# DHT11.net
KiCad netlist of a schematic drawn in Altium Designer
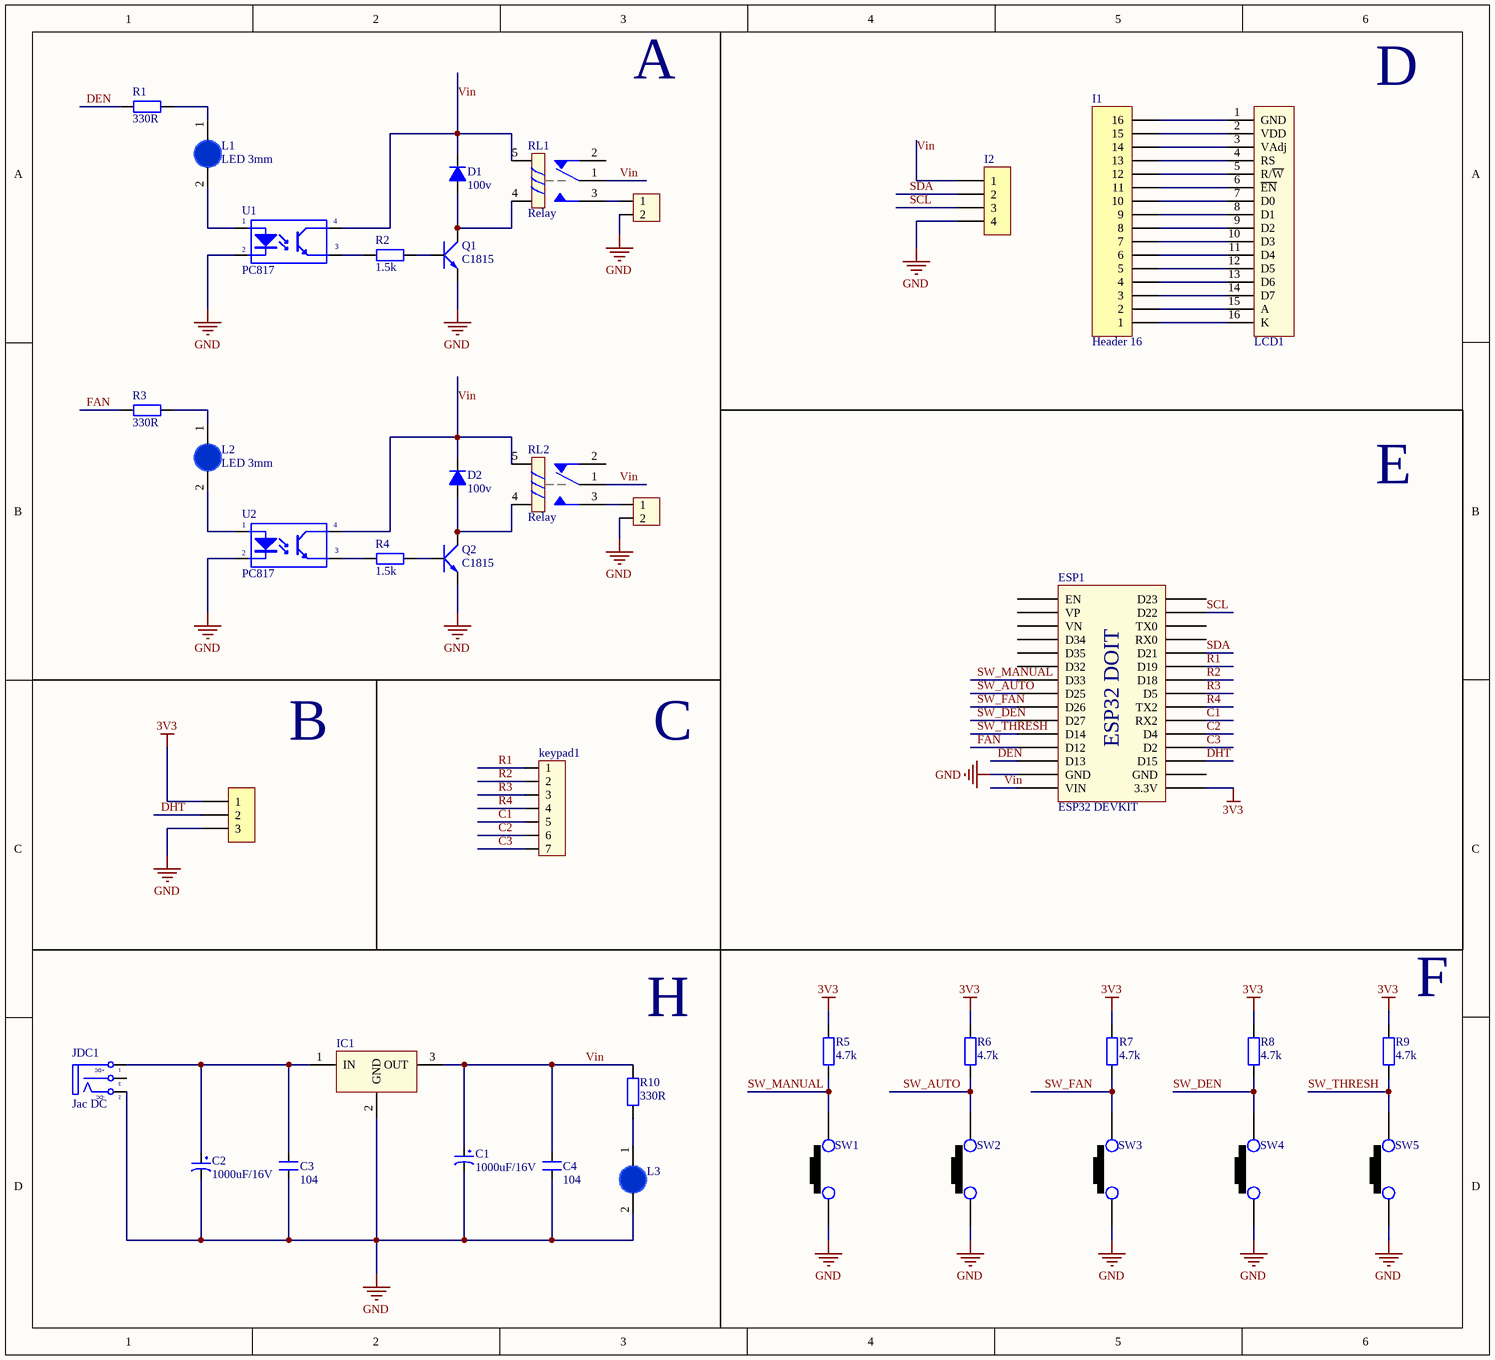
[diagram p0: DHT11.SchDoc]

(export (version "E")
  (design (tool "Eeschema 10.0.6"))
  (components
    (comp (ref "C1")
      (value "1000uF/16V")
      (footprint "CP1.5/3.4")
      (description "Cap 1000uF/16V - 220uF/50V")
      (libsource (lib "syhaunguyen") (part "CP4"))
    )
    (comp (ref "C2")
      (value "1000uF/16V")
      (footprint "CP1.5/3.4")
      (description "Cap 1000uF/16V - 220uF/50V")
      (libsource (lib "syhaunguyen") (part "CP4"))
    )
    (comp (ref "C3")
      (value "104")
      (footprint "CN2")
      (description "Cap np 104 => 105pF")
      (libsource (lib "syhaunguyen") (part "CN2"))
    )
    (comp (ref "C4")
      (value "104")
      (footprint "CN2")
      (description "Cap np 104 => 105pF")
      (libsource (lib "syhaunguyen") (part "CN2"))
    )
    (comp (ref "D1")
      (value "100v")
      (footprint "DIODE 1A")
      (description "Cắm")
      (libsource (lib "Altium_Lib_by_KhueNguyenCreator") (part "Diode 1N4007"))
    )
    (comp (ref "D2")
      (value "100v")
      (footprint "DIODE 1A")
      (description "Cắm")
      (libsource (lib "Altium_Lib_by_KhueNguyenCreator") (part "Diode 1N4007"))
    )
    (comp (ref "ESP1")
      (value "ESP32 DEVKIT")
      (footprint "ESP32 WROOM 32 KIT")
      (libsource (lib "Altium_Lib_by_KhueNguyenCreator") (part "ESP32 WROOM 32 KIT"))
    )
    (comp (ref "H1")
      (value "Header 2P 2.54 Duc Thang")
      (footprint "XH2.54M-2")
      (description "Cắm")
      (libsource (lib "Altium_Lib_by_KhueNguyenCreator") (part "Header 2P 2.54 Duc Thang"))
    )
    (comp (ref "H2")
      (value "Header 2P 2.54 Duc Thang")
      (footprint "XH2.54M-2")
      (description "Cắm")
      (libsource (lib "Altium_Lib_by_KhueNguyenCreator") (part "Header 2P 2.54 Duc Thang"))
    )
    (comp (ref "H3")
      (value "Header 3P 2.54 Duc Thang")
      (footprint "XH2.54M-3")
      (description "Cắm")
      (libsource (lib "Altium_Lib_by_KhueNguyenCreator") (part "Header 3P 2.54 Duc Thang"))
    )
    (comp (ref "I1")
      (value "Header 16")
      (footprint "HDR1X16")
      (description "Header, 16-Pin")
      (fields (field (name "PUBLISHER") "Altium Limited"))
      (libsource (lib "Schematic") (part "Header 16"))
    )
    (comp (ref "I2")
      (value "Header 4P 2.54 Duc Thang")
      (footprint "XH2.54M-4")
      (description "Cắm")
      (libsource (lib "Altium_Lib_by_KhueNguyenCreator") (part "Header 4P 2.54 Duc Thang"))
    )
    (comp (ref "IC1")
      (value "LM7805")
      (footprint "QTO-220")
      (description "On ap +, from + 5 to + 24VDC")
      (libsource (lib "syhaunguyen") (part "LM78xx"))
    )
    (comp (ref "JDC1")
      (value "Jac DC")
      (footprint "DC-IN")
      (description "Jac DC input")
      (libsource (lib "syhaunguyen") (part "DCIN"))
    )
    (comp (ref "keypad1")
      (value "Header 7P 2.54 Duc Thang")
      (footprint "XH2.54M-7")
      (description "Cắm")
      (libsource (lib "Altium_Lib_by_KhueNguyenCreator") (part "Header 7P 2.54 Duc Thang"))
    )
    (comp (ref "L1")
      (value "LED 3mm")
      (footprint "LED-3MM-BLUE")
      (description "Cắm")
      (libsource (lib "Altium_Lib_by_KhueNguyenCreator") (part "LED 3mm Xanh Duong"))
    )
    (comp (ref "L2")
      (value "LED 3mm")
      (footprint "LED-3MM-BLUE")
      (description "Cắm")
      (libsource (lib "Altium_Lib_by_KhueNguyenCreator") (part "LED 3mm Xanh Duong"))
    )
    (comp (ref "L3")
      (value "LED 3mm")
      (footprint "LED-3MM-BLUE")
      (description "Cắm")
      (libsource (lib "Altium_Lib_by_KhueNguyenCreator") (part "LED 3mm Xanh Duong"))
    )
    (comp (ref "LCD1")
      (value "LCD1602 XL")
      (footprint "LCD1602 with Jump")
      (description "LCD 1602 Xanh Lá")
      (libsource (lib "Altium_Lib_by_KhueNguyenCreator") (part "LCD1602 XL"))
    )
    (comp (ref "Q1")
      (value "C1815")
      (footprint "TO92")
      (description "NPN transistor")
      (libsource (lib "Altium_Lib_by_KhueNguyenCreator") (part "Trans C1815 DIP"))
    )
    (comp (ref "Q2")
      (value "C1815")
      (footprint "TO92")
      (description "NPN transistor")
      (libsource (lib "Altium_Lib_by_KhueNguyenCreator") (part "Trans C1815 DIP"))
    )
    (comp (ref "R1")
      (value "330R")
      (footprint "tro vach 1/2w")
      (description "Cắm")
      (libsource (lib "Altium_Lib_by_KhueNguyenCreator") (part "Tro Vach 1/2W 5% 330R"))
    )
    (comp (ref "R2")
      (value "1.5k")
      (footprint "tro vach 1/4w")
      (description "Cắm")
      (libsource (lib "Altium_Lib_by_KhueNguyenCreator") (part "Tro Vach 1/4W 5% 1.5k"))
    )
    (comp (ref "R3")
      (value "330R")
      (footprint "tro vach 1/2w")
      (description "Cắm")
      (libsource (lib "Altium_Lib_by_KhueNguyenCreator") (part "Tro Vach 1/2W 5% 330R"))
    )
    (comp (ref "R4")
      (value "1.5k")
      (footprint "tro vach 1/4w")
      (description "Cắm")
      (libsource (lib "Altium_Lib_by_KhueNguyenCreator") (part "Tro Vach 1/4W 5% 1.5k"))
    )
    (comp (ref "R5")
      (value "4.7k")
      (footprint "tro vach 1/2w")
      (description "Cắm")
      (libsource (lib "Altium_Lib_by_KhueNguyenCreator") (part "Tro Vach 1/2W 5% 4.7k"))
    )
    (comp (ref "R6")
      (value "4.7k")
      (footprint "tro vach 1/2w")
      (description "Cắm")
      (libsource (lib "Altium_Lib_by_KhueNguyenCreator") (part "Tro Vach 1/2W 5% 4.7k"))
    )
    (comp (ref "R7")
      (value "4.7k")
      (footprint "tro vach 1/2w")
      (description "Cắm")
      (libsource (lib "Altium_Lib_by_KhueNguyenCreator") (part "Tro Vach 1/2W 5% 4.7k"))
    )
    (comp (ref "R8")
      (value "4.7k")
      (footprint "tro vach 1/2w")
      (description "Cắm")
      (libsource (lib "Altium_Lib_by_KhueNguyenCreator") (part "Tro Vach 1/2W 5% 4.7k"))
    )
    (comp (ref "R9")
      (value "4.7k")
      (footprint "tro vach 1/2w")
      (description "Cắm")
      (libsource (lib "Altium_Lib_by_KhueNguyenCreator") (part "Tro Vach 1/2W 5% 4.7k"))
    )
    (comp (ref "R10")
      (value "330R")
      (footprint "tro vach 1/2w")
      (description "Cắm")
      (libsource (lib "Altium_Lib_by_KhueNguyenCreator") (part "Tro Vach 1/2W 5% 330R"))
    )
    (comp (ref "RL1")
      (value "Relay")
      (footprint "Relay 5 Chan SRD")
      (description "Relay 5 Chan")
      (libsource (lib "Altium_Lib_by_KhueNguyenCreator") (part "Relay 5 Chan SRD"))
    )
    (comp (ref "RL2")
      (value "Relay")
      (footprint "Relay 5 Chan SRD")
      (description "Relay 5 Chan")
      (libsource (lib "Altium_Lib_by_KhueNguyenCreator") (part "Relay 5 Chan SRD"))
    )
    (comp (ref "SW1")
      (value "TACTILE SWITCH")
      (footprint "SW_342_SMD")
      (description "Tactile Switch SPST-NO Top Actuated Surface Mount")
      (fields
        (field (name "MANUFACTURER") "ITT C&K")
        (field (name "MANUFACTURER PART NUMBER") "RS-282G05A3-SMRT")
      )
      (libsource (lib "Altium_Lib_by_KhueNguyenCreator") (part "SW1_RS-282G05A3-SMRT-SMD"))
    )
    (comp (ref "SW2")
      (value "TACTILE SWITCH")
      (footprint "SW_342_SMD")
      (description "Tactile Switch SPST-NO Top Actuated Surface Mount")
      (fields
        (field (name "MANUFACTURER") "ITT C&K")
        (field (name "MANUFACTURER PART NUMBER") "RS-282G05A3-SMRT")
      )
      (libsource (lib "Altium_Lib_by_KhueNguyenCreator") (part "SW1_RS-282G05A3-SMRT-SMD"))
    )
    (comp (ref "SW3")
      (value "TACTILE SWITCH")
      (footprint "SW_342_SMD")
      (description "Tactile Switch SPST-NO Top Actuated Surface Mount")
      (fields
        (field (name "MANUFACTURER") "ITT C&K")
        (field (name "MANUFACTURER PART NUMBER") "RS-282G05A3-SMRT")
      )
      (libsource (lib "Altium_Lib_by_KhueNguyenCreator") (part "SW1_RS-282G05A3-SMRT-SMD"))
    )
    (comp (ref "SW4")
      (value "TACTILE SWITCH")
      (footprint "SW_342_SMD")
      (description "Tactile Switch SPST-NO Top Actuated Surface Mount")
      (fields
        (field (name "MANUFACTURER") "ITT C&K")
        (field (name "MANUFACTURER PART NUMBER") "RS-282G05A3-SMRT")
      )
      (libsource (lib "Altium_Lib_by_KhueNguyenCreator") (part "SW1_RS-282G05A3-SMRT-SMD"))
    )
    (comp (ref "SW5")
      (value "TACTILE SWITCH")
      (footprint "SW_342_SMD")
      (description "Tactile Switch SPST-NO Top Actuated Surface Mount")
      (fields
        (field (name "MANUFACTURER") "ITT C&K")
        (field (name "MANUFACTURER PART NUMBER") "RS-282G05A3-SMRT")
      )
      (libsource (lib "Altium_Lib_by_KhueNguyenCreator") (part "SW1_RS-282G05A3-SMRT-SMD"))
    )
    (comp (ref "U1")
      (value "PC817")
      (footprint "PC817")
      (description "Single Opto")
      (libsource (lib "SCH_MyLib_0") (part "PC817_1"))
    )
    (comp (ref "U2")
      (value "PC817")
      (footprint "PC817")
      (description "Single Opto")
      (libsource (lib "SCH_MyLib_0") (part "PC817_1"))
    )
  )
  (nets
    (net (code "1") (name "/C1") (class "Default")
      (node (ref "ESP1") (pin "21") (pinfunction "RX2_21") (pintype "passive"))
      (node (ref "keypad1") (pin "5") (pinfunction "5_5") (pintype "passive"))
    )
    (net (code "2") (name "/C2") (class "Default")
      (node (ref "ESP1") (pin "20") (pinfunction "D4_20") (pintype "passive"))
      (node (ref "keypad1") (pin "6") (pinfunction "6_6") (pintype "passive"))
    )
    (net (code "3") (name "/C3") (class "Default")
      (node (ref "ESP1") (pin "19") (pinfunction "D2_19") (pintype "passive"))
      (node (ref "keypad1") (pin "7") (pinfunction "7_7") (pintype "passive"))
    )
    (net (code "4") (name "/DEN") (class "Default")
      (node (ref "ESP1") (pin "13") (pinfunction "D13_13") (pintype "passive"))
      (node (ref "R1") (pin "1") (pinfunction "1_1") (pintype "passive"))
    )
    (net (code "5") (name "/DHT") (class "Default")
      (node (ref "ESP1") (pin "18") (pinfunction "D15_18") (pintype "passive"))
      (node (ref "H3") (pin "2") (pinfunction "2_2") (pintype "passive"))
    )
    (net (code "6") (name "/FAN") (class "Default")
      (node (ref "ESP1") (pin "12") (pinfunction "D12_12") (pintype "passive"))
      (node (ref "R3") (pin "1") (pinfunction "1_1") (pintype "passive"))
    )
    (net (code "7") (name "/R1") (class "Default")
      (node (ref "ESP1") (pin "25") (pinfunction "D19_25") (pintype "passive"))
      (node (ref "keypad1") (pin "1") (pinfunction "1_1") (pintype "passive"))
    )
    (net (code "8") (name "/R2") (class "Default")
      (node (ref "ESP1") (pin "24") (pinfunction "D18_24") (pintype "passive"))
      (node (ref "keypad1") (pin "2") (pinfunction "2_2") (pintype "passive"))
    )
    (net (code "9") (name "/R3") (class "Default")
      (node (ref "ESP1") (pin "23") (pinfunction "D5_23") (pintype "passive"))
      (node (ref "keypad1") (pin "3") (pinfunction "3_3") (pintype "passive"))
    )
    (net (code "10") (name "/R4") (class "Default")
      (node (ref "ESP1") (pin "22") (pinfunction "TX2_22") (pintype "passive"))
      (node (ref "keypad1") (pin "4") (pinfunction "4_4") (pintype "passive"))
    )
    (net (code "11") (name "/SCL") (class "Default")
      (node (ref "ESP1") (pin "29") (pinfunction "D22_29") (pintype "passive"))
      (node (ref "I2") (pin "3") (pinfunction "3_3") (pintype "passive"))
    )
    (net (code "12") (name "/SDA") (class "Default")
      (node (ref "ESP1") (pin "26") (pinfunction "D21_26") (pintype "passive"))
      (node (ref "I2") (pin "2") (pinfunction "2_2") (pintype "passive"))
    )
    (net (code "13") (name "/SW_AUTO") (class "Default")
      (node (ref "ESP1") (pin "8") (pinfunction "D25_8") (pintype "passive"))
      (node (ref "R6") (pin "1") (pinfunction "1_1") (pintype "passive"))
      (node (ref "SW2") (pin "2") (pinfunction "2_2") (pintype "passive"))
    )
    (net (code "14") (name "/SW_DEN") (class "Default")
      (node (ref "ESP1") (pin "10") (pinfunction "D27_10") (pintype "passive"))
      (node (ref "R8") (pin "1") (pinfunction "1_1") (pintype "passive"))
      (node (ref "SW4") (pin "2") (pinfunction "2_2") (pintype "passive"))
    )
    (net (code "15") (name "/SW_FAN") (class "Default")
      (node (ref "ESP1") (pin "9") (pinfunction "D26_9") (pintype "passive"))
      (node (ref "R7") (pin "1") (pinfunction "1_1") (pintype "passive"))
      (node (ref "SW3") (pin "2") (pinfunction "2_2") (pintype "passive"))
    )
    (net (code "16") (name "/SW_MANUAL") (class "Default")
      (node (ref "ESP1") (pin "7") (pinfunction "D33_7") (pintype "passive"))
      (node (ref "R5") (pin "1") (pinfunction "1_1") (pintype "passive"))
      (node (ref "SW1") (pin "2") (pinfunction "2_2") (pintype "passive"))
    )
    (net (code "17") (name "/SW_THRESH") (class "Default")
      (node (ref "ESP1") (pin "11") (pinfunction "D14_11") (pintype "passive"))
      (node (ref "R9") (pin "1") (pinfunction "1_1") (pintype "passive"))
      (node (ref "SW5") (pin "2") (pinfunction "2_2") (pintype "passive"))
    )
    (net (code "18") (name "/Vin") (class "Default")
      (node (ref "C1") (pin "1") (pinfunction "1_1") (pintype "passive"))
      (node (ref "C4") (pin "2") (pinfunction "2_2") (pintype "passive"))
      (node (ref "D1") (pin "2") (pinfunction "K_2") (pintype "passive"))
      (node (ref "D2") (pin "2") (pinfunction "K_2") (pintype "passive"))
      (node (ref "ESP1") (pin "15") (pinfunction "VIN_15") (pintype "passive"))
      (node (ref "I2") (pin "1") (pinfunction "1_1") (pintype "passive"))
      (node (ref "IC1") (pin "3") (pinfunction "OUT_3") (pintype "passive"))
      (node (ref "R10") (pin "1") (pinfunction "1_1") (pintype "passive"))
      (node (ref "RL1") (pin "1") (pinfunction "1_1") (pintype "passive"))
      (node (ref "RL1") (pin "5") (pinfunction "5_5") (pintype "passive"))
      (node (ref "RL2") (pin "1") (pinfunction "1_1") (pintype "passive"))
      (node (ref "RL2") (pin "5") (pinfunction "5_5") (pintype "passive"))
      (node (ref "U1") (pin "4") (pinfunction "C_4") (pintype "passive"))
      (node (ref "U2") (pin "4") (pinfunction "C_4") (pintype "passive"))
    )
    (net (code "19") (name "3V3") (class "Default")
      (node (ref "ESP1") (pin "16") (pinfunction "3.3V_16") (pintype "passive"))
      (node (ref "H3") (pin "1") (pinfunction "1_1") (pintype "passive"))
      (node (ref "R5") (pin "2") (pinfunction "2_2") (pintype "passive"))
      (node (ref "R6") (pin "2") (pinfunction "2_2") (pintype "passive"))
      (node (ref "R7") (pin "2") (pinfunction "2_2") (pintype "passive"))
      (node (ref "R8") (pin "2") (pinfunction "2_2") (pintype "passive"))
      (node (ref "R9") (pin "2") (pinfunction "2_2") (pintype "passive"))
    )
    (net (code "20") (name "GND") (class "Default")
      (node (ref "C1") (pin "2") (pinfunction "2_2") (pintype "passive"))
      (node (ref "C2") (pin "2") (pinfunction "2_2") (pintype "passive"))
      (node (ref "C3") (pin "1") (pinfunction "1_1") (pintype "passive"))
      (node (ref "C4") (pin "1") (pinfunction "1_1") (pintype "passive"))
      (node (ref "ESP1") (pin "14") (pinfunction "GND_14") (pintype "passive"))
      (node (ref "H1") (pin "2") (pinfunction "2_2") (pintype "passive"))
      (node (ref "H2") (pin "2") (pinfunction "2_2") (pintype "passive"))
      (node (ref "H3") (pin "3") (pinfunction "3_3") (pintype "passive"))
      (node (ref "I2") (pin "4") (pinfunction "4_4") (pintype "passive"))
      (node (ref "IC1") (pin "2") (pinfunction "GND_2") (pintype "passive"))
      (node (ref "JDC1") (pin "2") (pinfunction "TN_2") (pintype "passive"))
      (node (ref "L3") (pin "2") (pinfunction "K_2") (pintype "passive"))
      (node (ref "Q1") (pin "1") (pinfunction "E_1") (pintype "passive"))
      (node (ref "Q2") (pin "1") (pinfunction "E_1") (pintype "passive"))
      (node (ref "SW1") (pin "1") (pinfunction "1_1") (pintype "passive"))
      (node (ref "SW2") (pin "1") (pinfunction "1_1") (pintype "passive"))
      (node (ref "SW3") (pin "1") (pinfunction "1_1") (pintype "passive"))
      (node (ref "SW4") (pin "1") (pinfunction "1_1") (pintype "passive"))
      (node (ref "SW5") (pin "1") (pinfunction "1_1") (pintype "passive"))
      (node (ref "U1") (pin "2") (pinfunction "K_2") (pintype "passive"))
      (node (ref "U2") (pin "2") (pinfunction "K_2") (pintype "passive"))
    )
    (net (code "21") (name "Net-(D1-A)") (class "Default")
      (node (ref "D1") (pin "1") (pinfunction "A_1") (pintype "passive"))
      (node (ref "Q1") (pin "2") (pinfunction "C_2") (pintype "passive"))
      (node (ref "RL1") (pin "4") (pinfunction "4_4") (pintype "passive"))
    )
    (net (code "22") (name "Net-(D2-A)") (class "Default")
      (node (ref "D2") (pin "1") (pinfunction "A_1") (pintype "passive"))
      (node (ref "Q2") (pin "2") (pinfunction "C_2") (pintype "passive"))
      (node (ref "RL2") (pin "4") (pinfunction "4_4") (pintype "passive"))
    )
    (net (code "23") (name "Net-(H1-Pad1)") (class "Default")
      (node (ref "H1") (pin "1") (pinfunction "1_1") (pintype "passive"))
      (node (ref "RL1") (pin "3") (pinfunction "3_3") (pintype "passive"))
    )
    (net (code "24") (name "Net-(H2-Pad1)") (class "Default")
      (node (ref "H2") (pin "1") (pinfunction "1_1") (pintype "passive"))
      (node (ref "RL2") (pin "3") (pinfunction "3_3") (pintype "passive"))
    )
    (net (code "25") (name "Net-(IC1-IN)") (class "Default")
      (node (ref "C2") (pin "1") (pinfunction "1_1") (pintype "passive"))
      (node (ref "C3") (pin "2") (pinfunction "2_2") (pintype "passive"))
      (node (ref "IC1") (pin "1") (pinfunction "IN_1") (pintype "passive"))
      (node (ref "JDC1") (pin "1") (pinfunction "T_1") (pintype "passive"))
    )
    (net (code "26") (name "Net-(L1-A)") (class "Default")
      (node (ref "L1") (pin "1") (pinfunction "A_1") (pintype "passive"))
      (node (ref "R1") (pin "2") (pinfunction "2_2") (pintype "passive"))
    )
    (net (code "27") (name "Net-(L1-K)") (class "Default")
      (node (ref "L1") (pin "2") (pinfunction "K_2") (pintype "passive"))
      (node (ref "U1") (pin "1") (pinfunction "A_1") (pintype "passive"))
    )
    (net (code "28") (name "Net-(L2-A)") (class "Default")
      (node (ref "L2") (pin "1") (pinfunction "A_1") (pintype "passive"))
      (node (ref "R3") (pin "2") (pinfunction "2_2") (pintype "passive"))
    )
    (net (code "29") (name "Net-(L2-K)") (class "Default")
      (node (ref "L2") (pin "2") (pinfunction "K_2") (pintype "passive"))
      (node (ref "U2") (pin "1") (pinfunction "A_1") (pintype "passive"))
    )
    (net (code "30") (name "Net-(L3-A)") (class "Default")
      (node (ref "L3") (pin "1") (pinfunction "A_1") (pintype "passive"))
      (node (ref "R10") (pin "2") (pinfunction "2_2") (pintype "passive"))
    )
    (net (code "31") (name "Net-(LCD1-A)") (class "Default")
      (node (ref "I1") (pin "2") (pinfunction "2_2") (pintype "passive"))
      (node (ref "LCD1") (pin "15") (pinfunction "A_15") (pintype "passive"))
    )
    (net (code "32") (name "Net-(LCD1-D0)") (class "Default")
      (node (ref "I1") (pin "10") (pinfunction "10_10") (pintype "passive"))
      (node (ref "LCD1") (pin "7") (pinfunction "D0_7") (pintype "passive"))
    )
    (net (code "33") (name "Net-(LCD1-D1)") (class "Default")
      (node (ref "I1") (pin "9") (pinfunction "9_9") (pintype "passive"))
      (node (ref "LCD1") (pin "8") (pinfunction "D1_8") (pintype "passive"))
    )
    (net (code "34") (name "Net-(LCD1-D2)") (class "Default")
      (node (ref "I1") (pin "8") (pinfunction "8_8") (pintype "passive"))
      (node (ref "LCD1") (pin "9") (pinfunction "D2_9") (pintype "passive"))
    )
    (net (code "35") (name "Net-(LCD1-D3)") (class "Default")
      (node (ref "I1") (pin "7") (pinfunction "7_7") (pintype "passive"))
      (node (ref "LCD1") (pin "10") (pinfunction "D3_10") (pintype "passive"))
    )
    (net (code "36") (name "Net-(LCD1-D4)") (class "Default")
      (node (ref "I1") (pin "6") (pinfunction "6_6") (pintype "passive"))
      (node (ref "LCD1") (pin "11") (pinfunction "D4_11") (pintype "passive"))
    )
    (net (code "37") (name "Net-(LCD1-D5)") (class "Default")
      (node (ref "I1") (pin "5") (pinfunction "5_5") (pintype "passive"))
      (node (ref "LCD1") (pin "12") (pinfunction "D5_12") (pintype "passive"))
    )
    (net (code "38") (name "Net-(LCD1-D6)") (class "Default")
      (node (ref "I1") (pin "4") (pinfunction "4_4") (pintype "passive"))
      (node (ref "LCD1") (pin "13") (pinfunction "D6_13") (pintype "passive"))
    )
    (net (code "39") (name "Net-(LCD1-D7)") (class "Default")
      (node (ref "I1") (pin "3") (pinfunction "3_3") (pintype "passive"))
      (node (ref "LCD1") (pin "14") (pinfunction "D7_14") (pintype "passive"))
    )
    (net (code "40") (name "Net-(LCD1-GND)") (class "Default")
      (node (ref "I1") (pin "16") (pinfunction "16_16") (pintype "passive"))
      (node (ref "LCD1") (pin "1") (pinfunction "GND_1") (pintype "passive"))
    )
    (net (code "41") (name "Net-(LCD1-K)") (class "Default")
      (node (ref "I1") (pin "1") (pinfunction "1_1") (pintype "passive"))
      (node (ref "LCD1") (pin "16") (pinfunction "K_16") (pintype "passive"))
    )
    (net (code "42") (name "Net-(LCD1-RS)") (class "Default")
      (node (ref "I1") (pin "13") (pinfunction "13_13") (pintype "passive"))
      (node (ref "LCD1") (pin "4") (pinfunction "RS_4") (pintype "passive"))
    )
    (net (code "43") (name "Net-(LCD1-R{slash}~{W})") (class "Default")
      (node (ref "I1") (pin "12") (pinfunction "12_12") (pintype "passive"))
      (node (ref "LCD1") (pin "5") (pinfunction "R/~{W}_5") (pintype "passive"))
    )
    (net (code "44") (name "Net-(LCD1-VAdj)") (class "Default")
      (node (ref "I1") (pin "14") (pinfunction "14_14") (pintype "passive"))
      (node (ref "LCD1") (pin "3") (pinfunction "VAdj_3") (pintype "passive"))
    )
    (net (code "45") (name "Net-(LCD1-VDD)") (class "Default")
      (node (ref "I1") (pin "15") (pinfunction "15_15") (pintype "passive"))
      (node (ref "LCD1") (pin "2") (pinfunction "VDD_2") (pintype "passive"))
    )
    (net (code "46") (name "Net-(LCD1-~{EN})") (class "Default")
      (node (ref "I1") (pin "11") (pinfunction "11_11") (pintype "passive"))
      (node (ref "LCD1") (pin "6") (pinfunction "~{EN}_6") (pintype "passive"))
    )
    (net (code "47") (name "Net-(Q1-B)") (class "Default")
      (node (ref "Q1") (pin "3") (pinfunction "B_3") (pintype "passive"))
      (node (ref "R2") (pin "2") (pinfunction "2_2") (pintype "passive"))
    )
    (net (code "48") (name "Net-(Q2-B)") (class "Default")
      (node (ref "Q2") (pin "3") (pinfunction "B_3") (pintype "passive"))
      (node (ref "R4") (pin "2") (pinfunction "2_2") (pintype "passive"))
    )
    (net (code "49") (name "Net-(U1-E)") (class "Default")
      (node (ref "R2") (pin "1") (pinfunction "1_1") (pintype "passive"))
      (node (ref "U1") (pin "3") (pinfunction "E_3") (pintype "passive"))
    )
    (net (code "50") (name "Net-(U2-E)") (class "Default")
      (node (ref "R4") (pin "1") (pinfunction "1_1") (pintype "passive"))
      (node (ref "U2") (pin "3") (pinfunction "E_3") (pintype "passive"))
    )
    (net (code "51") (name "unconnected-(ESP1-D23-Pad30)") (class "Default")
      (node (ref "ESP1") (pin "30") (pinfunction "D23_30") (pintype "passive"))
    )
    (net (code "52") (name "unconnected-(ESP1-D32-Pad6)") (class "Default")
      (node (ref "ESP1") (pin "6") (pinfunction "D32_6") (pintype "passive"))
    )
    (net (code "53") (name "unconnected-(ESP1-D34-Pad4)") (class "Default")
      (node (ref "ESP1") (pin "4") (pinfunction "D34_4") (pintype "passive"))
    )
    (net (code "54") (name "unconnected-(ESP1-D35-Pad5)") (class "Default")
      (node (ref "ESP1") (pin "5") (pinfunction "D35_5") (pintype "passive"))
    )
    (net (code "55") (name "unconnected-(ESP1-EN-Pad1)") (class "Default")
      (node (ref "ESP1") (pin "1") (pinfunction "EN_1") (pintype "passive"))
    )
    (net (code "56") (name "unconnected-(ESP1-GND-Pad17)") (class "Default")
      (node (ref "ESP1") (pin "17") (pinfunction "GND_17") (pintype "passive"))
    )
    (net (code "57") (name "unconnected-(ESP1-RX0-Pad27)") (class "Default")
      (node (ref "ESP1") (pin "27") (pinfunction "RX0_27") (pintype "passive"))
    )
    (net (code "58") (name "unconnected-(ESP1-TX0-Pad28)") (class "Default")
      (node (ref "ESP1") (pin "28") (pinfunction "TX0_28") (pintype "passive"))
    )
    (net (code "59") (name "unconnected-(ESP1-VN-Pad3)") (class "Default")
      (node (ref "ESP1") (pin "3") (pinfunction "VN_3") (pintype "passive"))
    )
    (net (code "60") (name "unconnected-(ESP1-VP-Pad2)") (class "Default")
      (node (ref "ESP1") (pin "2") (pinfunction "VP_2") (pintype "passive"))
    )
    (net (code "61") (name "unconnected-(JDC1-S-Pad3)") (class "Default")
      (node (ref "JDC1") (pin "3") (pinfunction "S_3") (pintype "power_in"))
    )
    (net (code "62") (name "unconnected-(RL1-Pad2)") (class "Default")
      (node (ref "RL1") (pin "2") (pinfunction "2_2") (pintype "passive"))
    )
    (net (code "63") (name "unconnected-(RL2-Pad2)") (class "Default")
      (node (ref "RL2") (pin "2") (pinfunction "2_2") (pintype "passive"))
    )
  )
)
